# PMB_LED.net
KiCad netlist of a schematic drawn in EAGLE
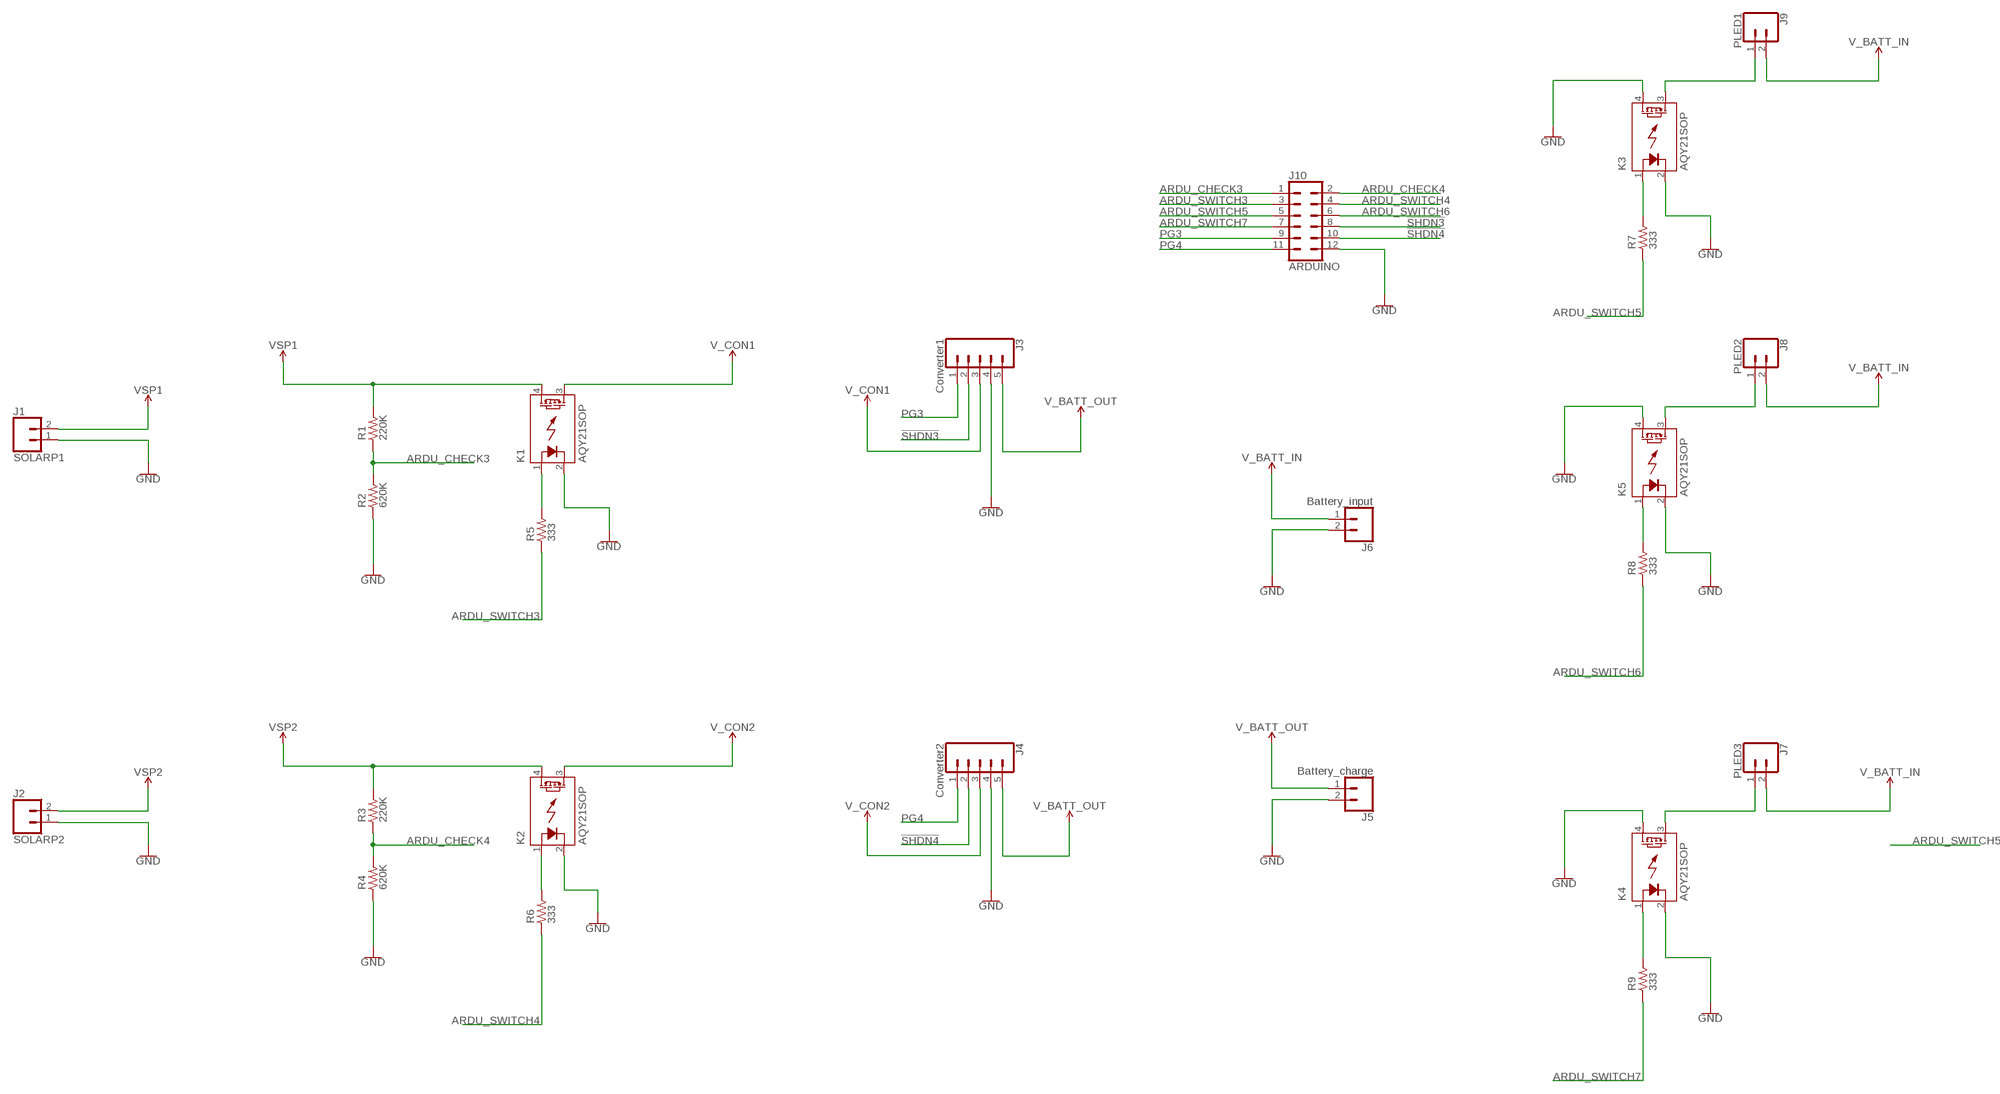
[diagram p0: schematic, sheet 1]

(export (version "E")
  (design (tool "Eeschema 10.0.6"))
  (components
    (comp (ref "J1")
      (value "SOLARP1")
      (footprint "eagle-import:1X02_LONGPADS")
      (libsource (lib "eagle-import") (part "CONN_02PTH3"))
    )
    (comp (ref "J2")
      (value "SOLARP2")
      (footprint "eagle-import:1X02_LONGPADS")
      (libsource (lib "eagle-import") (part "CONN_02PTH3"))
    )
    (comp (ref "J3")
      (value "Converter1")
      (footprint "eagle-import:1X05_LONGPADS")
      (libsource (lib "eagle-import") (part "CONN_05PTH_LONGPADS"))
    )
    (comp (ref "J4")
      (value "Converter2")
      (footprint "eagle-import:1X05_LONGPADS")
      (libsource (lib "eagle-import") (part "CONN_05PTH_LONGPADS"))
    )
    (comp (ref "J5")
      (value "Battery_charge")
      (footprint "eagle-import:1X02_LOCK_LONGPADS")
      (libsource (lib "eagle-import") (part "CONN_02LOCK_LONGPADS"))
    )
    (comp (ref "J6")
      (value "Battery_input")
      (footprint "eagle-import:1X02_LOCK_LONGPADS")
      (libsource (lib "eagle-import") (part "CONN_02LOCK_LONGPADS"))
    )
    (comp (ref "J7")
      (value "PLED3")
      (footprint "eagle-import:1X02")
      (libsource (lib "eagle-import") (part "CONN_02"))
    )
    (comp (ref "J8")
      (value "PLED2")
      (footprint "eagle-import:1X02")
      (libsource (lib "eagle-import") (part "CONN_02"))
    )
    (comp (ref "J9")
      (value "PLED1")
      (footprint "eagle-import:1X02")
      (libsource (lib "eagle-import") (part "CONN_02"))
    )
    (comp (ref "J10")
      (value "ARDUINO")
      (footprint "eagle-import:2X6")
      (libsource (lib "eagle-import") (part "CONN_06X2PTH_FEMALE"))
    )
    (comp (ref "K1")
      (value "AQY21SOP")
      (footprint "eagle-import:SOP04")
      (libsource (lib "eagle-import") (part "AQYSOP21"))
    )
    (comp (ref "K2")
      (value "AQY21SOP")
      (footprint "eagle-import:SOP04")
      (libsource (lib "eagle-import") (part "AQYSOP21"))
    )
    (comp (ref "K3")
      (value "AQY21SOP")
      (footprint "eagle-import:SOP04")
      (libsource (lib "eagle-import") (part "AQYSOP21"))
    )
    (comp (ref "K4")
      (value "AQY21SOP")
      (footprint "eagle-import:SOP04")
      (libsource (lib "eagle-import") (part "AQYSOP21"))
    )
    (comp (ref "K5")
      (value "AQY21SOP")
      (footprint "eagle-import:SOP04")
      (libsource (lib "eagle-import") (part "AQYSOP21"))
    )
    (comp (ref "R1")
      (value "220K")
      (footprint "eagle-import:R1206")
      (libsource (lib "eagle-import") (part "R_1206"))
    )
    (comp (ref "R2")
      (value "620K")
      (footprint "eagle-import:R1206")
      (libsource (lib "eagle-import") (part "R_1206"))
    )
    (comp (ref "R3")
      (value "220K")
      (footprint "eagle-import:R1206")
      (libsource (lib "eagle-import") (part "R_1206"))
    )
    (comp (ref "R4")
      (value "620K")
      (footprint "eagle-import:R1206")
      (libsource (lib "eagle-import") (part "R_1206"))
    )
    (comp (ref "R5")
      (value "333")
      (footprint "eagle-import:R1206")
      (libsource (lib "eagle-import") (part "R_1206"))
    )
    (comp (ref "R6")
      (value "333")
      (footprint "eagle-import:R1206")
      (libsource (lib "eagle-import") (part "R_1206"))
    )
    (comp (ref "R7")
      (value "333")
      (footprint "eagle-import:R1206")
      (libsource (lib "eagle-import") (part "R_1206"))
    )
    (comp (ref "R8")
      (value "333")
      (footprint "eagle-import:R1206")
      (libsource (lib "eagle-import") (part "R_1206"))
    )
    (comp (ref "R9")
      (value "333")
      (footprint "eagle-import:R1206")
      (libsource (lib "eagle-import") (part "R_1206"))
    )
  )
  (nets
    (net (code "1") (name "/ARDU_CHECK3") (class "Default")
      (node (ref "J10") (pin "1") (pinfunction "1_1") (pintype "passive"))
      (node (ref "R1") (pin "1") (pinfunction "1_1") (pintype "passive"))
      (node (ref "R2") (pin "2") (pinfunction "2_2") (pintype "passive"))
    )
    (net (code "2") (name "/ARDU_CHECK4") (class "Default")
      (node (ref "J10") (pin "2") (pinfunction "2_2") (pintype "passive"))
      (node (ref "R3") (pin "1") (pinfunction "1_1") (pintype "passive"))
      (node (ref "R4") (pin "2") (pinfunction "2_2") (pintype "passive"))
    )
    (net (code "3") (name "/ARDU_SWITCH3") (class "Default")
      (node (ref "J10") (pin "3") (pinfunction "3_3") (pintype "passive"))
      (node (ref "R5") (pin "1") (pinfunction "1_1") (pintype "passive"))
    )
    (net (code "4") (name "/ARDU_SWITCH4") (class "Default")
      (node (ref "J10") (pin "4") (pinfunction "4_4") (pintype "passive"))
      (node (ref "R6") (pin "1") (pinfunction "1_1") (pintype "passive"))
    )
    (net (code "5") (name "/ARDU_SWITCH5") (class "Default")
      (node (ref "J10") (pin "5") (pinfunction "5_5") (pintype "passive"))
      (node (ref "R7") (pin "1") (pinfunction "1_1") (pintype "passive"))
    )
    (net (code "6") (name "/ARDU_SWITCH6") (class "Default")
      (node (ref "J10") (pin "6") (pinfunction "6_6") (pintype "passive"))
      (node (ref "R8") (pin "1") (pinfunction "1_1") (pintype "passive"))
    )
    (net (code "7") (name "/ARDU_SWITCH7") (class "Default")
      (node (ref "J10") (pin "7") (pinfunction "7_7") (pintype "passive"))
      (node (ref "R9") (pin "1") (pinfunction "1_1") (pintype "passive"))
    )
    (net (code "8") (name "/PG3") (class "Default")
      (node (ref "J10") (pin "9") (pinfunction "9_9") (pintype "passive"))
      (node (ref "J3") (pin "1") (pinfunction "1_1") (pintype "passive"))
    )
    (net (code "9") (name "/PG4") (class "Default")
      (node (ref "J10") (pin "11") (pinfunction "11_11") (pintype "passive"))
      (node (ref "J4") (pin "1") (pinfunction "1_1") (pintype "passive"))
    )
    (net (code "10") (name "/~{SHDN3}") (class "Default")
      (node (ref "J10") (pin "8") (pinfunction "8_8") (pintype "passive"))
      (node (ref "J3") (pin "2") (pinfunction "2_2") (pintype "passive"))
    )
    (net (code "11") (name "/~{SHDN4}") (class "Default")
      (node (ref "J10") (pin "10") (pinfunction "10_10") (pintype "passive"))
      (node (ref "J4") (pin "2") (pinfunction "2_2") (pintype "passive"))
    )
    (net (code "12") (name "GND") (class "Default")
      (node (ref "J1") (pin "1") (pinfunction "1_1") (pintype "passive"))
      (node (ref "J10") (pin "12") (pinfunction "12_12") (pintype "passive"))
      (node (ref "J2") (pin "1") (pinfunction "1_1") (pintype "passive"))
      (node (ref "J3") (pin "4") (pinfunction "4_4") (pintype "passive"))
      (node (ref "J4") (pin "4") (pinfunction "4_4") (pintype "passive"))
      (node (ref "J5") (pin "2") (pinfunction "2_2") (pintype "passive"))
      (node (ref "J6") (pin "2") (pinfunction "2_2") (pintype "passive"))
      (node (ref "K1") (pin "2") (pinfunction "K_2") (pintype "passive"))
      (node (ref "K2") (pin "2") (pinfunction "K_2") (pintype "passive"))
      (node (ref "K3") (pin "2") (pinfunction "K_2") (pintype "passive"))
      (node (ref "K3") (pin "4") (pinfunction "DS1_4") (pintype "passive"))
      (node (ref "K4") (pin "2") (pinfunction "K_2") (pintype "passive"))
      (node (ref "K4") (pin "4") (pinfunction "DS1_4") (pintype "passive"))
      (node (ref "K5") (pin "2") (pinfunction "K_2") (pintype "passive"))
      (node (ref "K5") (pin "4") (pinfunction "DS1_4") (pintype "passive"))
      (node (ref "R2") (pin "1") (pinfunction "1_1") (pintype "passive"))
      (node (ref "R4") (pin "1") (pinfunction "1_1") (pintype "passive"))
    )
    (net (code "13") (name "Net-(K1-A)") (class "Default")
      (node (ref "K1") (pin "1") (pinfunction "A_1") (pintype "passive"))
      (node (ref "R5") (pin "2") (pinfunction "2_2") (pintype "passive"))
    )
    (net (code "14") (name "Net-(K2-A)") (class "Default")
      (node (ref "K2") (pin "1") (pinfunction "A_1") (pintype "passive"))
      (node (ref "R6") (pin "2") (pinfunction "2_2") (pintype "passive"))
    )
    (net (code "15") (name "Net-(K3-A)") (class "Default")
      (node (ref "K3") (pin "1") (pinfunction "A_1") (pintype "passive"))
      (node (ref "R7") (pin "2") (pinfunction "2_2") (pintype "passive"))
    )
    (net (code "16") (name "Net-(K3-DS2)") (class "Default")
      (node (ref "J9") (pin "1") (pinfunction "1_1") (pintype "passive"))
      (node (ref "K3") (pin "3") (pinfunction "DS2_3") (pintype "passive"))
    )
    (net (code "17") (name "Net-(K4-A)") (class "Default")
      (node (ref "K4") (pin "1") (pinfunction "A_1") (pintype "passive"))
      (node (ref "R9") (pin "2") (pinfunction "2_2") (pintype "passive"))
    )
    (net (code "18") (name "Net-(K4-DS2)") (class "Default")
      (node (ref "J7") (pin "1") (pinfunction "1_1") (pintype "passive"))
      (node (ref "K4") (pin "3") (pinfunction "DS2_3") (pintype "passive"))
    )
    (net (code "19") (name "Net-(K5-A)") (class "Default")
      (node (ref "K5") (pin "1") (pinfunction "A_1") (pintype "passive"))
      (node (ref "R8") (pin "2") (pinfunction "2_2") (pintype "passive"))
    )
    (net (code "20") (name "Net-(K5-DS2)") (class "Default")
      (node (ref "J8") (pin "1") (pinfunction "1_1") (pintype "passive"))
      (node (ref "K5") (pin "3") (pinfunction "DS2_3") (pintype "passive"))
    )
    (net (code "21") (name "VSP1") (class "Default")
      (node (ref "J1") (pin "2") (pinfunction "2_2") (pintype "passive"))
      (node (ref "K1") (pin "4") (pinfunction "DS1_4") (pintype "passive"))
      (node (ref "R1") (pin "2") (pinfunction "2_2") (pintype "passive"))
    )
    (net (code "22") (name "VSP2") (class "Default")
      (node (ref "J2") (pin "2") (pinfunction "2_2") (pintype "passive"))
      (node (ref "K2") (pin "4") (pinfunction "DS1_4") (pintype "passive"))
      (node (ref "R3") (pin "2") (pinfunction "2_2") (pintype "passive"))
    )
    (net (code "23") (name "V_BATT_IN") (class "Default")
      (node (ref "J6") (pin "1") (pinfunction "1_1") (pintype "passive"))
      (node (ref "J7") (pin "2") (pinfunction "2_2") (pintype "passive"))
      (node (ref "J8") (pin "2") (pinfunction "2_2") (pintype "passive"))
      (node (ref "J9") (pin "2") (pinfunction "2_2") (pintype "passive"))
    )
    (net (code "24") (name "V_BATT_OUT") (class "Default")
      (node (ref "J3") (pin "5") (pinfunction "5_5") (pintype "passive"))
      (node (ref "J4") (pin "5") (pinfunction "5_5") (pintype "passive"))
      (node (ref "J5") (pin "1") (pinfunction "1_1") (pintype "passive"))
    )
    (net (code "25") (name "V_CON1") (class "Default")
      (node (ref "J3") (pin "3") (pinfunction "3_3") (pintype "passive"))
      (node (ref "K1") (pin "3") (pinfunction "DS2_3") (pintype "passive"))
    )
    (net (code "26") (name "V_CON2") (class "Default")
      (node (ref "J4") (pin "3") (pinfunction "3_3") (pintype "passive"))
      (node (ref "K2") (pin "3") (pinfunction "DS2_3") (pintype "passive"))
    )
  )
)
